# control.net
KiCad netlist of a schematic drawn in EAGLE
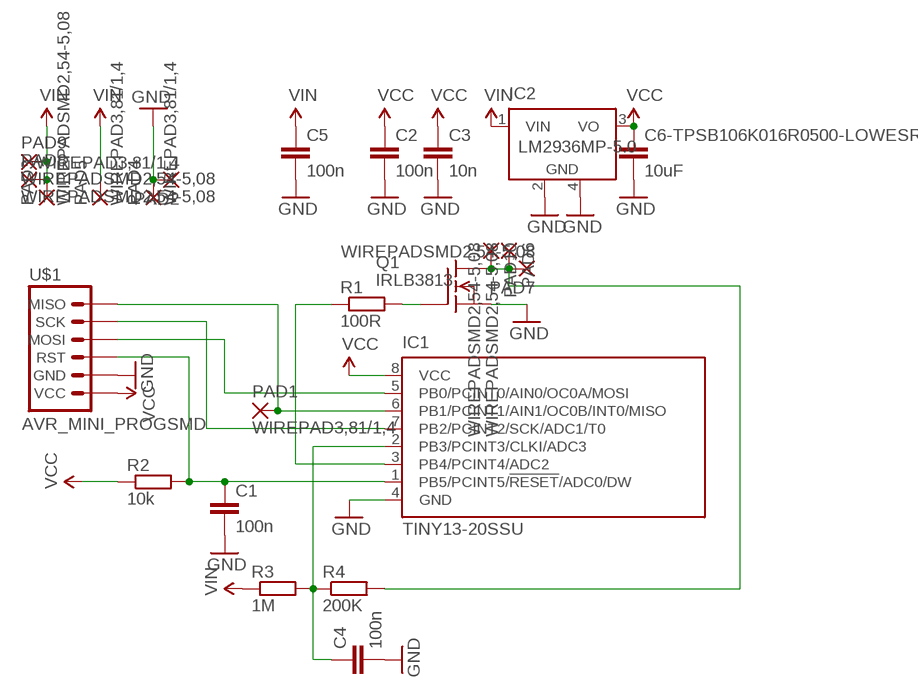
[diagram p0: schematic, sheet 1]

(export (version "E")
  (design (tool "Eeschema 10.0.6"))
  (components
    (comp (ref "C1")
      (value "100n")
      (footprint "eagle-import:1210")
      (libsource (lib "eagle-import") (part "CAP1210"))
    )
    (comp (ref "C2")
      (value "100n")
      (footprint "eagle-import:1206")
      (libsource (lib "eagle-import") (part "CAP1206"))
    )
    (comp (ref "C3")
      (value "10n")
      (footprint "eagle-import:1206")
      (libsource (lib "eagle-import") (part "CAP1206"))
    )
    (comp (ref "C4")
      (value "100n")
      (footprint "eagle-import:1206")
      (libsource (lib "eagle-import") (part "CAP1206"))
    )
    (comp (ref "C5")
      (value "100n")
      (footprint "eagle-import:1206")
      (libsource (lib "eagle-import") (part "CAP1206"))
    )
    (comp (ref "C6-TPSB106K016R0500-LOWESR")
      (value "10uF")
      (footprint "eagle-import:C1210")
      (libsource (lib "eagle-import") (part "C-EUC1210"))
    )
    (comp (ref "IC1")
      (value "TINY13-20SSU")
      (footprint "eagle-import:8S1")
      (fields (field (name "MPN") "ATTINY13-20SSU"))
      (libsource (lib "eagle-import") (part "TINY13SSU-20"))
    )
    (comp (ref "IC2")
      (value "LM2936MP-5.0")
      (footprint "eagle-import:SOT223")
      (fields (field (name "MF") "NATIONAL SEMICONDUCTOR") (field (name "MPN") "LM2936MP-5.0/NOPB"))
      (libsource (lib "eagle-import") (part "LM2936MP?-5.0"))
    )
    (comp (ref "PAD1")
      (value "WIREPAD3,81/1,4")
      (footprint "eagle-import:3,81_1,4")
      (libsource (lib "eagle-import") (part "WIREPAD3,81/1,4"))
    )
    (comp (ref "PAD2")
      (value "WIREPAD3,81/1,4")
      (footprint "eagle-import:3,81_1,4")
      (libsource (lib "eagle-import") (part "WIREPAD3,81/1,4"))
    )
    (comp (ref "PAD3")
      (value "WIREPADSMD2,54-5,08")
      (footprint "eagle-import:SMD2,54-5,08")
      (libsource (lib "eagle-import") (part "WIREPADSMD2,54-5,08"))
    )
    (comp (ref "PAD4")
      (value "WIREPAD3,81/1,4")
      (footprint "eagle-import:3,81_1,4")
      (libsource (lib "eagle-import") (part "WIREPAD3,81/1,4"))
    )
    (comp (ref "PAD5")
      (value "WIREPAD3,81/1,4")
      (footprint "eagle-import:3,81_1,4")
      (libsource (lib "eagle-import") (part "WIREPAD3,81/1,4"))
    )
    (comp (ref "PAD6")
      (value "WIREPADSMD2,54-5,08")
      (footprint "eagle-import:SMD2,54-5,08")
      (libsource (lib "eagle-import") (part "WIREPADSMD2,54-5,08"))
    )
    (comp (ref "PAD7")
      (value "WIREPADSMD2,54-5,08")
      (footprint "eagle-import:SMD2,54-5,08")
      (libsource (lib "eagle-import") (part "WIREPADSMD2,54-5,08"))
    )
    (comp (ref "PAD8")
      (value "WIREPADSMD2,54-5,08")
      (footprint "eagle-import:SMD2,54-5,08")
      (libsource (lib "eagle-import") (part "WIREPADSMD2,54-5,08"))
    )
    (comp (ref "PAD9")
      (value "WIREPADSMD2,54-5,08")
      (footprint "eagle-import:SMD2,54-5,08")
      (libsource (lib "eagle-import") (part "WIREPADSMD2,54-5,08"))
    )
    (comp (ref "PAD10")
      (value "WIREPADSMD2,54-5,08")
      (footprint "eagle-import:SMD2,54-5,08")
      (libsource (lib "eagle-import") (part "WIREPADSMD2,54-5,08"))
    )
    (comp (ref "Q1")
      (value "IRLB3813")
      (footprint "eagle-import:TO220")
      (libsource (lib "eagle-import") (part "IRF540"))
    )
    (comp (ref "R1")
      (value "100R")
      (footprint "eagle-import:M1206")
      (libsource (lib "eagle-import") (part "R-EU_M1206"))
    )
    (comp (ref "R2")
      (value "10k")
      (footprint "eagle-import:R1206")
      (libsource (lib "eagle-import") (part "R-EU_R1206"))
    )
    (comp (ref "R3")
      (value "1M")
      (footprint "eagle-import:M1206")
      (libsource (lib "eagle-import") (part "R-EU_M1206"))
    )
    (comp (ref "R4")
      (value "200K")
      (footprint "eagle-import:M1206")
      (libsource (lib "eagle-import") (part "R-EU_M1206"))
    )
    (comp (ref "U$1")
      (value "AVR_MINI_PROGSMD")
      (footprint "eagle-import:AVR_MINI_PROG")
      (libsource (lib "eagle-import") (part "AVR_MINI_PROGSMD"))
    )
  )
  (nets
    (net (code "1") (name "GND") (class "Default")
      (node (ref "C1") (pin "2") (pinfunction "2_2") (pintype "passive"))
      (node (ref "C2") (pin "2") (pinfunction "2_2") (pintype "passive"))
      (node (ref "C3") (pin "2") (pinfunction "2_2") (pintype "passive"))
      (node (ref "C4") (pin "2") (pinfunction "2_2") (pintype "passive"))
      (node (ref "C5") (pin "2") (pinfunction "2_2") (pintype "passive"))
      (node (ref "C6-TPSB106K016R0500-LOWESR") (pin "2") (pinfunction "2_2") (pintype "passive"))
      (node (ref "IC1") (pin "4") (pinfunction "GND_4") (pintype "power_in"))
      (node (ref "IC2") (pin "2") (pinfunction "GND_2") (pintype "passive"))
      (node (ref "IC2") (pin "4") (pinfunction "GND_4") (pintype "passive"))
      (node (ref "PAD2") (pin "1") (pinfunction "P_1") (pintype "passive"))
      (node (ref "PAD4") (pin "1") (pinfunction "P_1") (pintype "passive"))
      (node (ref "Q1") (pin "3") (pinfunction "S_3") (pintype "passive"))
      (node (ref "U$1") (pin "2") (pinfunction "GND_2") (pintype "passive"))
    )
    (net (code "2") (name "Net-(IC1-PB0{slash}PCINT0{slash}AIN0{slash}OC0A{slash}MOSI)") (class "Default")
      (node (ref "IC1") (pin "5") (pinfunction "PB0/PCINT0/AIN0/OC0A/MOSI_5") (pintype "bidirectional"))
      (node (ref "U$1") (pin "4") (pinfunction "MOSI_4") (pintype "passive"))
    )
    (net (code "3") (name "Net-(IC1-PB1{slash}PCINT1{slash}AIN1{slash}OC0B{slash}INT0{slash}MISO)") (class "Default")
      (node (ref "IC1") (pin "6") (pinfunction "PB1/PCINT1/AIN1/OC0B/INT0/MISO_6") (pintype "bidirectional"))
      (node (ref "PAD1") (pin "1") (pinfunction "P_1") (pintype "passive"))
      (node (ref "U$1") (pin "6") (pinfunction "MISO_6") (pintype "passive"))
    )
    (net (code "4") (name "Net-(IC1-PB2{slash}PCINT2{slash}SCK{slash}ADC1{slash}T0)") (class "Default")
      (node (ref "IC1") (pin "7") (pinfunction "PB2/PCINT2/SCK/ADC1/T0_7") (pintype "bidirectional"))
      (node (ref "U$1") (pin "5") (pinfunction "SCK_5") (pintype "passive"))
    )
    (net (code "5") (name "Net-(IC1-PB3{slash}PCINT3{slash}CLKI{slash}ADC3)") (class "Default")
      (node (ref "C4") (pin "1") (pinfunction "1_1") (pintype "passive"))
      (node (ref "IC1") (pin "2") (pinfunction "PB3/PCINT3/CLKI/ADC3_2") (pintype "bidirectional"))
      (node (ref "R3") (pin "2") (pinfunction "2_2") (pintype "passive"))
      (node (ref "R4") (pin "1") (pinfunction "1_1") (pintype "passive"))
    )
    (net (code "6") (name "Net-(IC1-PB4{slash}PCINT4{slash}ADC2)") (class "Default")
      (node (ref "IC1") (pin "3") (pinfunction "PB4/PCINT4/ADC2_3") (pintype "bidirectional"))
      (node (ref "R1") (pin "1") (pinfunction "1_1") (pintype "passive"))
    )
    (net (code "7") (name "Net-(IC1-PB5{slash}PCINT5{slash}~{RESET}{slash}ADC0{slash}DW)") (class "Default")
      (node (ref "C1") (pin "1") (pinfunction "1_1") (pintype "passive"))
      (node (ref "IC1") (pin "1") (pinfunction "PB5/PCINT5/~{RESET}/ADC0/DW_1") (pintype "bidirectional"))
      (node (ref "R2") (pin "2") (pinfunction "2_2") (pintype "passive"))
      (node (ref "U$1") (pin "3") (pinfunction "RST_3") (pintype "passive"))
    )
    (net (code "8") (name "Net-(PAD10-P)") (class "Default")
      (node (ref "PAD10") (pin "1") (pinfunction "P_1") (pintype "passive"))
      (node (ref "PAD6") (pin "1") (pinfunction "P_1") (pintype "passive"))
      (node (ref "PAD7") (pin "1") (pinfunction "P_1") (pintype "passive"))
      (node (ref "Q1") (pin "2") (pinfunction "D_2") (pintype "passive"))
      (node (ref "R4") (pin "2") (pinfunction "2_2") (pintype "passive"))
    )
    (net (code "9") (name "Net-(Q1-G)") (class "Default")
      (node (ref "Q1") (pin "1") (pinfunction "G_1") (pintype "passive"))
      (node (ref "R1") (pin "2") (pinfunction "2_2") (pintype "passive"))
    )
    (net (code "10") (name "VCC") (class "Default")
      (node (ref "C2") (pin "1") (pinfunction "1_1") (pintype "passive"))
      (node (ref "C3") (pin "1") (pinfunction "1_1") (pintype "passive"))
      (node (ref "C6-TPSB106K016R0500-LOWESR") (pin "1") (pinfunction "1_1") (pintype "passive"))
      (node (ref "IC1") (pin "8") (pinfunction "VCC_8") (pintype "power_in"))
      (node (ref "IC2") (pin "3") (pinfunction "VO_3") (pintype "passive"))
      (node (ref "R2") (pin "1") (pinfunction "1_1") (pintype "passive"))
      (node (ref "U$1") (pin "1") (pinfunction "VCC_1") (pintype "passive"))
    )
    (net (code "11") (name "VIN") (class "Default")
      (node (ref "C5") (pin "1") (pinfunction "1_1") (pintype "passive"))
      (node (ref "IC2") (pin "1") (pinfunction "VIN_1") (pintype "input"))
      (node (ref "PAD3") (pin "1") (pinfunction "P_1") (pintype "passive"))
      (node (ref "PAD5") (pin "1") (pinfunction "P_1") (pintype "passive"))
      (node (ref "PAD8") (pin "1") (pinfunction "P_1") (pintype "passive"))
      (node (ref "PAD9") (pin "1") (pinfunction "P_1") (pintype "passive"))
      (node (ref "R3") (pin "1") (pinfunction "1_1") (pintype "passive"))
    )
  )
)
